# LED_letter_H.net
KiCad netlist of a schematic drawn in EAGLE
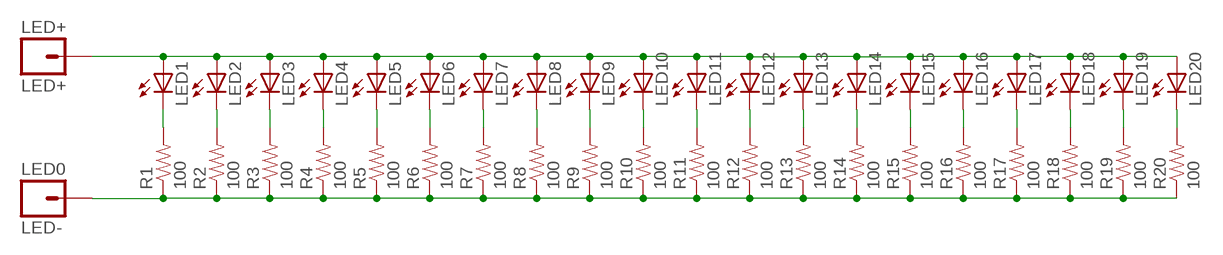
[diagram p0: schematic, sheet 1]

(export (version "E")
  (design (tool "Eeschema 10.0.6"))
  (components
    (comp (ref "LED+")
      (value "LED+")
      (footprint "eagle-import:1X01_OFFSET")
      (libsource (lib "eagle-import") (part "M01OFFSET"))
    )
    (comp (ref "LED0")
      (value "LED-")
      (footprint "eagle-import:1X01_OFFSET")
      (libsource (lib "eagle-import") (part "M01OFFSET"))
    )
    (comp (ref "LED1")
      (value "LED5MM")
      (footprint "eagle-import:LED5MM")
      (libsource (lib "eagle-import") (part "LED5MM"))
    )
    (comp (ref "LED2")
      (value "LED5MM")
      (footprint "eagle-import:LED5MM")
      (libsource (lib "eagle-import") (part "LED5MM"))
    )
    (comp (ref "LED3")
      (value "LED5MM")
      (footprint "eagle-import:LED5MM")
      (libsource (lib "eagle-import") (part "LED5MM"))
    )
    (comp (ref "LED4")
      (value "LED5MM")
      (footprint "eagle-import:LED5MM")
      (libsource (lib "eagle-import") (part "LED5MM"))
    )
    (comp (ref "LED5")
      (value "LED5MM")
      (footprint "eagle-import:LED5MM")
      (libsource (lib "eagle-import") (part "LED5MM"))
    )
    (comp (ref "LED6")
      (value "LED5MM")
      (footprint "eagle-import:LED5MM")
      (libsource (lib "eagle-import") (part "LED5MM"))
    )
    (comp (ref "LED7")
      (value "LED5MM")
      (footprint "eagle-import:LED5MM")
      (libsource (lib "eagle-import") (part "LED5MM"))
    )
    (comp (ref "LED8")
      (value "LED5MM")
      (footprint "eagle-import:LED5MM")
      (libsource (lib "eagle-import") (part "LED5MM"))
    )
    (comp (ref "LED9")
      (value "LED5MM")
      (footprint "eagle-import:LED5MM")
      (libsource (lib "eagle-import") (part "LED5MM"))
    )
    (comp (ref "LED10")
      (value "LED5MM")
      (footprint "eagle-import:LED5MM")
      (libsource (lib "eagle-import") (part "LED5MM"))
    )
    (comp (ref "LED11")
      (value "LED5MM")
      (footprint "eagle-import:LED5MM")
      (libsource (lib "eagle-import") (part "LED5MM"))
    )
    (comp (ref "LED12")
      (value "LED5MM")
      (footprint "eagle-import:LED5MM")
      (libsource (lib "eagle-import") (part "LED5MM"))
    )
    (comp (ref "LED13")
      (value "LED5MM")
      (footprint "eagle-import:LED5MM")
      (libsource (lib "eagle-import") (part "LED5MM"))
    )
    (comp (ref "LED14")
      (value "LED5MM")
      (footprint "eagle-import:LED5MM")
      (libsource (lib "eagle-import") (part "LED5MM"))
    )
    (comp (ref "LED15")
      (value "LED5MM")
      (footprint "eagle-import:LED5MM")
      (libsource (lib "eagle-import") (part "LED5MM"))
    )
    (comp (ref "LED16")
      (value "LED5MM")
      (footprint "eagle-import:LED5MM")
      (libsource (lib "eagle-import") (part "LED5MM"))
    )
    (comp (ref "LED17")
      (value "LED5MM")
      (footprint "eagle-import:LED5MM")
      (libsource (lib "eagle-import") (part "LED5MM"))
    )
    (comp (ref "LED18")
      (value "LED5MM")
      (footprint "eagle-import:LED5MM")
      (libsource (lib "eagle-import") (part "LED5MM"))
    )
    (comp (ref "LED19")
      (value "LED5MM")
      (footprint "eagle-import:LED5MM")
      (libsource (lib "eagle-import") (part "LED5MM"))
    )
    (comp (ref "LED20")
      (value "LED5MM")
      (footprint "eagle-import:LED5MM")
      (libsource (lib "eagle-import") (part "LED5MM"))
    )
    (comp (ref "R1")
      (value "100")
      (footprint "eagle-import:1_6W-RES")
      (libsource (lib "eagle-import") (part "RESISTORPTH-1/6W"))
    )
    (comp (ref "R2")
      (value "100")
      (footprint "eagle-import:1_6W-RES")
      (libsource (lib "eagle-import") (part "RESISTORPTH-1/6W"))
    )
    (comp (ref "R3")
      (value "100")
      (footprint "eagle-import:1_6W-RES")
      (libsource (lib "eagle-import") (part "RESISTORPTH-1/6W"))
    )
    (comp (ref "R4")
      (value "100")
      (footprint "eagle-import:1_6W-RES")
      (libsource (lib "eagle-import") (part "RESISTORPTH-1/6W"))
    )
    (comp (ref "R5")
      (value "100")
      (footprint "eagle-import:1_6W-RES")
      (libsource (lib "eagle-import") (part "RESISTORPTH-1/6W"))
    )
    (comp (ref "R6")
      (value "100")
      (footprint "eagle-import:1_6W-RES")
      (libsource (lib "eagle-import") (part "RESISTORPTH-1/6W"))
    )
    (comp (ref "R7")
      (value "100")
      (footprint "eagle-import:1_6W-RES")
      (libsource (lib "eagle-import") (part "RESISTORPTH-1/6W"))
    )
    (comp (ref "R8")
      (value "100")
      (footprint "eagle-import:1_6W-RES")
      (libsource (lib "eagle-import") (part "RESISTORPTH-1/6W"))
    )
    (comp (ref "R9")
      (value "100")
      (footprint "eagle-import:1_6W-RES")
      (libsource (lib "eagle-import") (part "RESISTORPTH-1/6W"))
    )
    (comp (ref "R10")
      (value "100")
      (footprint "eagle-import:1_6W-RES")
      (libsource (lib "eagle-import") (part "RESISTORPTH-1/6W"))
    )
    (comp (ref "R11")
      (value "100")
      (footprint "eagle-import:1_6W-RES")
      (libsource (lib "eagle-import") (part "RESISTORPTH-1/6W"))
    )
    (comp (ref "R12")
      (value "100")
      (footprint "eagle-import:1_6W-RES")
      (libsource (lib "eagle-import") (part "RESISTORPTH-1/6W"))
    )
    (comp (ref "R13")
      (value "100")
      (footprint "eagle-import:1_6W-RES")
      (libsource (lib "eagle-import") (part "RESISTORPTH-1/6W"))
    )
    (comp (ref "R14")
      (value "100")
      (footprint "eagle-import:1_6W-RES")
      (libsource (lib "eagle-import") (part "RESISTORPTH-1/6W"))
    )
    (comp (ref "R15")
      (value "100")
      (footprint "eagle-import:1_6W-RES")
      (libsource (lib "eagle-import") (part "RESISTORPTH-1/6W"))
    )
    (comp (ref "R16")
      (value "100")
      (footprint "eagle-import:1_6W-RES")
      (libsource (lib "eagle-import") (part "RESISTORPTH-1/6W"))
    )
    (comp (ref "R17")
      (value "100")
      (footprint "eagle-import:1_6W-RES")
      (libsource (lib "eagle-import") (part "RESISTORPTH-1/6W"))
    )
    (comp (ref "R18")
      (value "100")
      (footprint "eagle-import:1_6W-RES")
      (libsource (lib "eagle-import") (part "RESISTORPTH-1/6W"))
    )
    (comp (ref "R19")
      (value "100")
      (footprint "eagle-import:1_6W-RES")
      (libsource (lib "eagle-import") (part "RESISTORPTH-1/6W"))
    )
    (comp (ref "R20")
      (value "100")
      (footprint "eagle-import:1_6W-RES")
      (libsource (lib "eagle-import") (part "RESISTORPTH-1/6W"))
    )
  )
  (nets
    (net (code "1") (name "Net-(LED+-Pad1)") (class "Default")
      (node (ref "LED+") (pin "1") (pinfunction "1_1") (pintype "passive"))
      (node (ref "LED1") (pin "A") (pinfunction "A_A") (pintype "passive"))
      (node (ref "LED10") (pin "A") (pinfunction "A_A") (pintype "passive"))
      (node (ref "LED11") (pin "A") (pinfunction "A_A") (pintype "passive"))
      (node (ref "LED12") (pin "A") (pinfunction "A_A") (pintype "passive"))
      (node (ref "LED13") (pin "A") (pinfunction "A_A") (pintype "passive"))
      (node (ref "LED14") (pin "A") (pinfunction "A_A") (pintype "passive"))
      (node (ref "LED15") (pin "A") (pinfunction "A_A") (pintype "passive"))
      (node (ref "LED16") (pin "A") (pinfunction "A_A") (pintype "passive"))
      (node (ref "LED17") (pin "A") (pinfunction "A_A") (pintype "passive"))
      (node (ref "LED18") (pin "A") (pinfunction "A_A") (pintype "passive"))
      (node (ref "LED19") (pin "A") (pinfunction "A_A") (pintype "passive"))
      (node (ref "LED2") (pin "A") (pinfunction "A_A") (pintype "passive"))
      (node (ref "LED20") (pin "A") (pinfunction "A_A") (pintype "passive"))
      (node (ref "LED3") (pin "A") (pinfunction "A_A") (pintype "passive"))
      (node (ref "LED4") (pin "A") (pinfunction "A_A") (pintype "passive"))
      (node (ref "LED5") (pin "A") (pinfunction "A_A") (pintype "passive"))
      (node (ref "LED6") (pin "A") (pinfunction "A_A") (pintype "passive"))
      (node (ref "LED7") (pin "A") (pinfunction "A_A") (pintype "passive"))
      (node (ref "LED8") (pin "A") (pinfunction "A_A") (pintype "passive"))
      (node (ref "LED9") (pin "A") (pinfunction "A_A") (pintype "passive"))
    )
    (net (code "2") (name "Net-(LED0-Pad1)") (class "Default")
      (node (ref "LED0") (pin "1") (pinfunction "1_1") (pintype "passive"))
      (node (ref "R1") (pin "1") (pinfunction "1_1") (pintype "passive"))
      (node (ref "R10") (pin "1") (pinfunction "1_1") (pintype "passive"))
      (node (ref "R11") (pin "1") (pinfunction "1_1") (pintype "passive"))
      (node (ref "R12") (pin "1") (pinfunction "1_1") (pintype "passive"))
      (node (ref "R13") (pin "1") (pinfunction "1_1") (pintype "passive"))
      (node (ref "R14") (pin "1") (pinfunction "1_1") (pintype "passive"))
      (node (ref "R15") (pin "1") (pinfunction "1_1") (pintype "passive"))
      (node (ref "R16") (pin "1") (pinfunction "1_1") (pintype "passive"))
      (node (ref "R17") (pin "1") (pinfunction "1_1") (pintype "passive"))
      (node (ref "R18") (pin "1") (pinfunction "1_1") (pintype "passive"))
      (node (ref "R19") (pin "1") (pinfunction "1_1") (pintype "passive"))
      (node (ref "R2") (pin "1") (pinfunction "1_1") (pintype "passive"))
      (node (ref "R20") (pin "1") (pinfunction "1_1") (pintype "passive"))
      (node (ref "R3") (pin "1") (pinfunction "1_1") (pintype "passive"))
      (node (ref "R4") (pin "1") (pinfunction "1_1") (pintype "passive"))
      (node (ref "R5") (pin "1") (pinfunction "1_1") (pintype "passive"))
      (node (ref "R6") (pin "1") (pinfunction "1_1") (pintype "passive"))
      (node (ref "R7") (pin "1") (pinfunction "1_1") (pintype "passive"))
      (node (ref "R8") (pin "1") (pinfunction "1_1") (pintype "passive"))
      (node (ref "R9") (pin "1") (pinfunction "1_1") (pintype "passive"))
    )
    (net (code "3") (name "Net-(LED1-C)") (class "Default")
      (node (ref "LED1") (pin "K") (pinfunction "C_K") (pintype "passive"))
      (node (ref "R1") (pin "2") (pinfunction "2_2") (pintype "passive"))
    )
    (net (code "4") (name "Net-(LED2-C)") (class "Default")
      (node (ref "LED2") (pin "K") (pinfunction "C_K") (pintype "passive"))
      (node (ref "R2") (pin "2") (pinfunction "2_2") (pintype "passive"))
    )
    (net (code "5") (name "Net-(LED3-C)") (class "Default")
      (node (ref "LED3") (pin "K") (pinfunction "C_K") (pintype "passive"))
      (node (ref "R3") (pin "2") (pinfunction "2_2") (pintype "passive"))
    )
    (net (code "6") (name "Net-(LED4-C)") (class "Default")
      (node (ref "LED4") (pin "K") (pinfunction "C_K") (pintype "passive"))
      (node (ref "R4") (pin "2") (pinfunction "2_2") (pintype "passive"))
    )
    (net (code "7") (name "Net-(LED5-C)") (class "Default")
      (node (ref "LED5") (pin "K") (pinfunction "C_K") (pintype "passive"))
      (node (ref "R5") (pin "2") (pinfunction "2_2") (pintype "passive"))
    )
    (net (code "8") (name "Net-(LED6-C)") (class "Default")
      (node (ref "LED6") (pin "K") (pinfunction "C_K") (pintype "passive"))
      (node (ref "R6") (pin "2") (pinfunction "2_2") (pintype "passive"))
    )
    (net (code "9") (name "Net-(LED7-C)") (class "Default")
      (node (ref "LED7") (pin "K") (pinfunction "C_K") (pintype "passive"))
      (node (ref "R7") (pin "2") (pinfunction "2_2") (pintype "passive"))
    )
    (net (code "10") (name "Net-(LED8-C)") (class "Default")
      (node (ref "LED8") (pin "K") (pinfunction "C_K") (pintype "passive"))
      (node (ref "R8") (pin "2") (pinfunction "2_2") (pintype "passive"))
    )
    (net (code "11") (name "Net-(LED9-C)") (class "Default")
      (node (ref "LED9") (pin "K") (pinfunction "C_K") (pintype "passive"))
      (node (ref "R9") (pin "2") (pinfunction "2_2") (pintype "passive"))
    )
    (net (code "12") (name "Net-(LED10-C)") (class "Default")
      (node (ref "LED10") (pin "K") (pinfunction "C_K") (pintype "passive"))
      (node (ref "R10") (pin "2") (pinfunction "2_2") (pintype "passive"))
    )
    (net (code "13") (name "Net-(LED11-C)") (class "Default")
      (node (ref "LED11") (pin "K") (pinfunction "C_K") (pintype "passive"))
      (node (ref "R11") (pin "2") (pinfunction "2_2") (pintype "passive"))
    )
    (net (code "14") (name "Net-(LED12-C)") (class "Default")
      (node (ref "LED12") (pin "K") (pinfunction "C_K") (pintype "passive"))
      (node (ref "R12") (pin "2") (pinfunction "2_2") (pintype "passive"))
    )
    (net (code "15") (name "Net-(LED13-C)") (class "Default")
      (node (ref "LED13") (pin "K") (pinfunction "C_K") (pintype "passive"))
      (node (ref "R13") (pin "2") (pinfunction "2_2") (pintype "passive"))
    )
    (net (code "16") (name "Net-(LED14-C)") (class "Default")
      (node (ref "LED14") (pin "K") (pinfunction "C_K") (pintype "passive"))
      (node (ref "R14") (pin "2") (pinfunction "2_2") (pintype "passive"))
    )
    (net (code "17") (name "Net-(LED15-C)") (class "Default")
      (node (ref "LED15") (pin "K") (pinfunction "C_K") (pintype "passive"))
      (node (ref "R15") (pin "2") (pinfunction "2_2") (pintype "passive"))
    )
    (net (code "18") (name "Net-(LED16-C)") (class "Default")
      (node (ref "LED16") (pin "K") (pinfunction "C_K") (pintype "passive"))
      (node (ref "R16") (pin "2") (pinfunction "2_2") (pintype "passive"))
    )
    (net (code "19") (name "Net-(LED17-C)") (class "Default")
      (node (ref "LED17") (pin "K") (pinfunction "C_K") (pintype "passive"))
      (node (ref "R17") (pin "2") (pinfunction "2_2") (pintype "passive"))
    )
    (net (code "20") (name "Net-(LED18-C)") (class "Default")
      (node (ref "LED18") (pin "K") (pinfunction "C_K") (pintype "passive"))
      (node (ref "R18") (pin "2") (pinfunction "2_2") (pintype "passive"))
    )
    (net (code "21") (name "Net-(LED19-C)") (class "Default")
      (node (ref "LED19") (pin "K") (pinfunction "C_K") (pintype "passive"))
      (node (ref "R19") (pin "2") (pinfunction "2_2") (pintype "passive"))
    )
    (net (code "22") (name "Net-(LED20-C)") (class "Default")
      (node (ref "LED20") (pin "K") (pinfunction "C_K") (pintype "passive"))
      (node (ref "R20") (pin "2") (pinfunction "2_2") (pintype "passive"))
    )
  )
)
